# SparkFun_Ambient_Light_Sensor_VEML6030.net
KiCad netlist of a schematic drawn in EAGLE
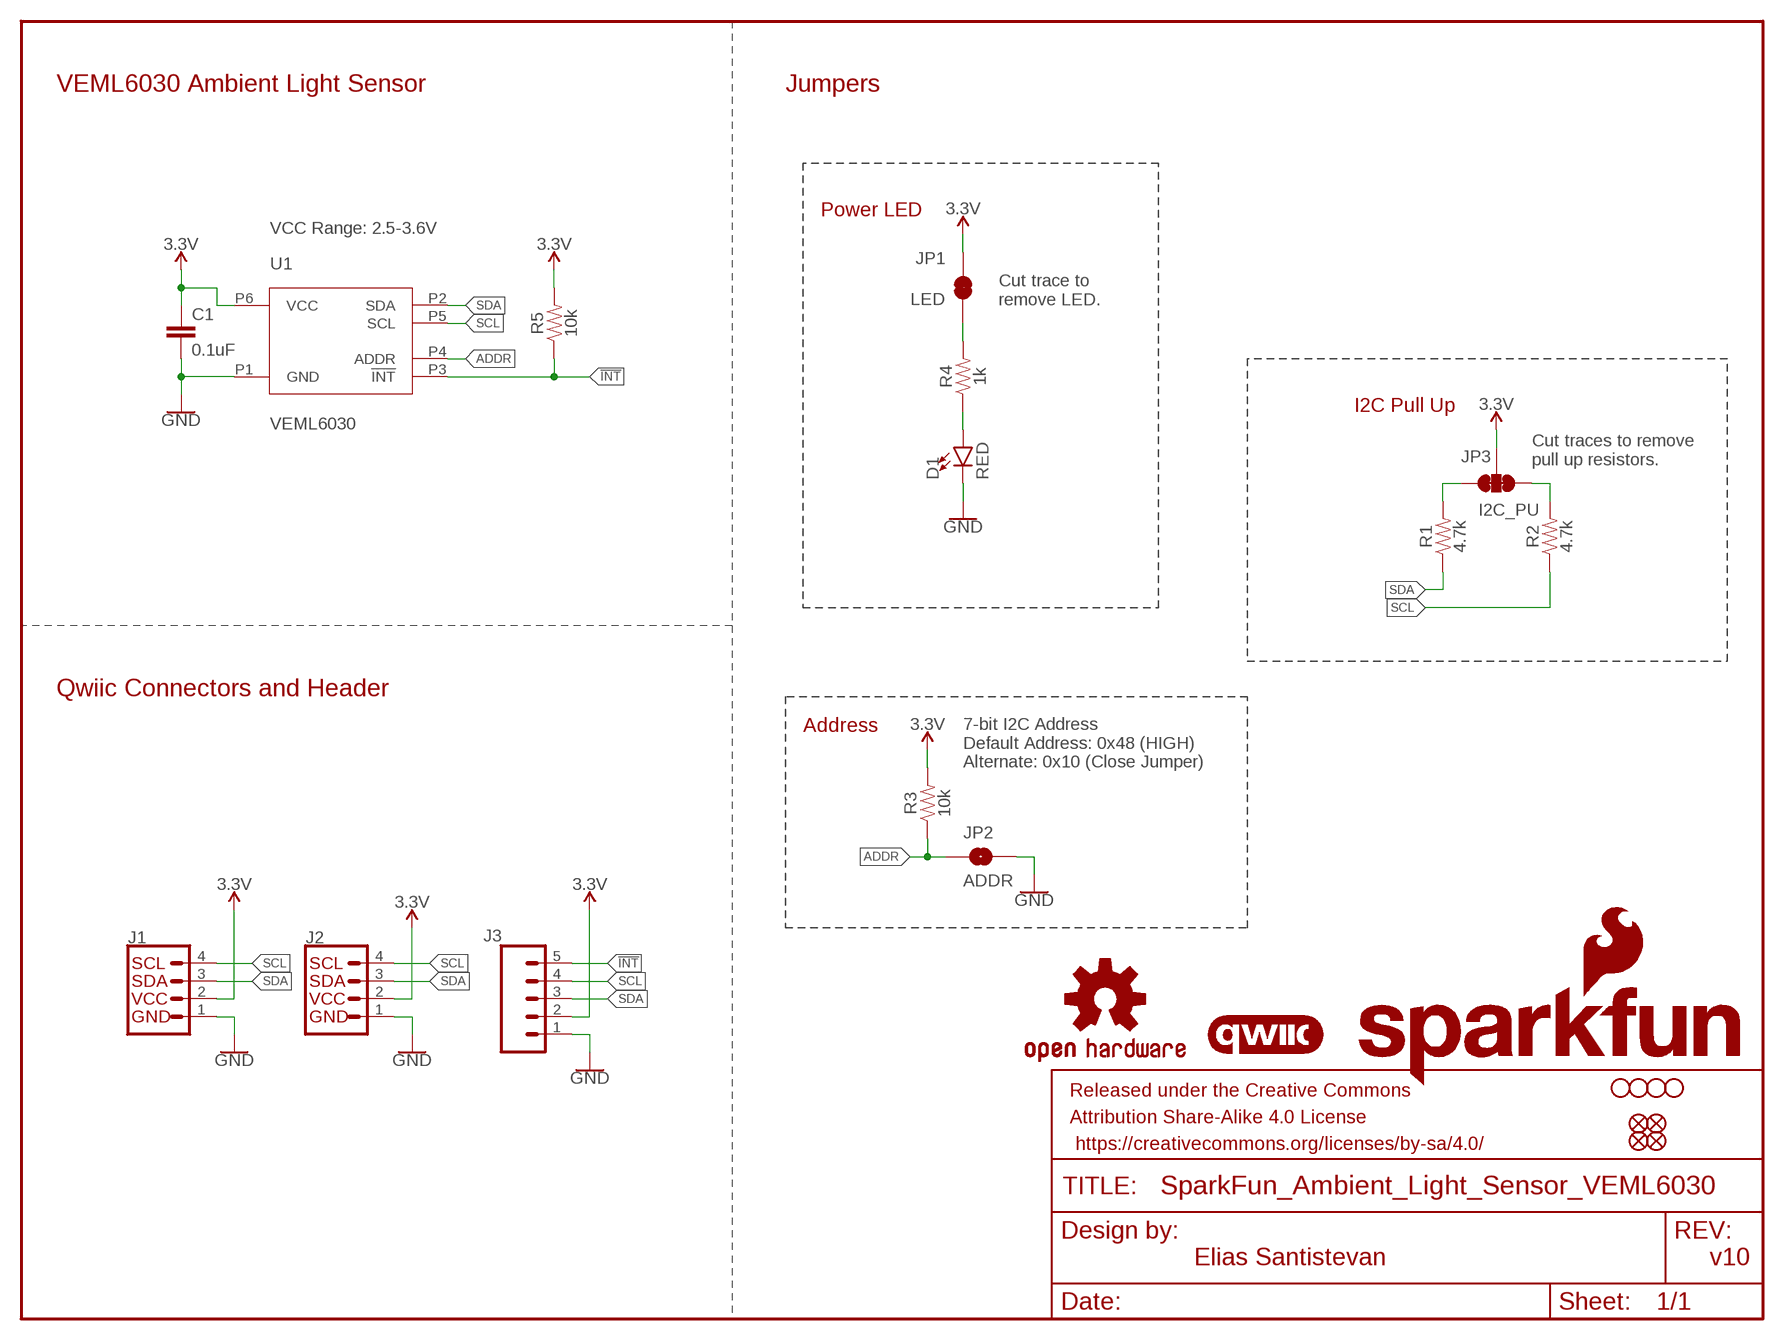
[diagram p0: schematic, sheet 1]

(export (version "E")
  (design (tool "Eeschema 10.0.6"))
  (components
    (comp (ref "C1")
      (value "0.1uF")
      (footprint "eagle-import:0603")
      (libsource (lib "eagle-import") (part "0.1UF-0603-25V-(+80/-20%)"))
    )
    (comp (ref "D1")
      (value "RED")
      (footprint "eagle-import:LED-0603")
      (libsource (lib "eagle-import") (part "LED-RED0603"))
    )
    (comp (ref "FD1")
      (value "FIDUCIAL1X2")
      (footprint "eagle-import:FIDUCIAL-1X2")
      (libsource (lib "eagle-import") (part "FIDUCIAL1X2"))
    )
    (comp (ref "FD2")
      (value "FIDUCIAL1X2")
      (footprint "eagle-import:FIDUCIAL-1X2")
      (libsource (lib "eagle-import") (part "FIDUCIAL1X2"))
    )
    (comp (ref "FD3")
      (value "FIDUCIAL1X2")
      (footprint "eagle-import:FIDUCIAL-1X2")
      (libsource (lib "eagle-import") (part "FIDUCIAL1X2"))
    )
    (comp (ref "FD4")
      (value "FIDUCIAL1X2")
      (footprint "eagle-import:FIDUCIAL-1X2")
      (libsource (lib "eagle-import") (part "FIDUCIAL1X2"))
    )
    (comp (ref "FRAME1")
      (value "FRAME-LETTER")
      (footprint "eagle-import:CREATIVE_COMMONS")
      (libsource (lib "eagle-import") (part "FRAME-LETTER"))
    )
    (comp (ref "H1")
      (value "STAND-OFFTIGHT")
      (footprint "eagle-import:STAND-OFF-TIGHT")
      (libsource (lib "eagle-import") (part "STAND-OFFTIGHT"))
    )
    (comp (ref "H2")
      (value "STAND-OFFTIGHT")
      (footprint "eagle-import:STAND-OFF-TIGHT")
      (libsource (lib "eagle-import") (part "STAND-OFFTIGHT"))
    )
    (comp (ref "H3")
      (value "STAND-OFFTIGHT")
      (footprint "eagle-import:STAND-OFF-TIGHT")
      (libsource (lib "eagle-import") (part "STAND-OFFTIGHT"))
    )
    (comp (ref "H4")
      (value "STAND-OFFTIGHT")
      (footprint "eagle-import:STAND-OFF-TIGHT")
      (libsource (lib "eagle-import") (part "STAND-OFFTIGHT"))
    )
    (comp (ref "J1")
      (value "QWIIC_CONNECTORJS-1MM")
      (footprint "eagle-import:JST04_1MM_RA")
      (libsource (lib "eagle-import") (part "QWIIC_CONNECTORJS-1MM"))
    )
    (comp (ref "J2")
      (value "QWIIC_CONNECTORJS-1MM")
      (footprint "eagle-import:JST04_1MM_RA")
      (libsource (lib "eagle-import") (part "QWIIC_CONNECTORJS-1MM"))
    )
    (comp (ref "J3")
      (value "CONN_05NO_SILK")
      (footprint "eagle-import:1X05_NO_SILK")
      (libsource (lib "eagle-import") (part "CONN_05NO_SILK"))
    )
    (comp (ref "JP1")
      (value "LED")
      (footprint "eagle-import:SMT-JUMPER_2_NC_TRACE_SILK")
      (libsource (lib "eagle-import") (part "JUMPER-SMT_2_NC_TRACE_SILK"))
    )
    (comp (ref "JP2")
      (value "ADDR")
      (footprint "eagle-import:SMT-JUMPER_2_NO_SILK")
      (libsource (lib "eagle-import") (part "JUMPER-SMT_2_NO_SILK"))
    )
    (comp (ref "JP3")
      (value "I2C_PU")
      (footprint "eagle-import:SMT-JUMPER_3_2-NC_TRACE_SILK")
      (libsource (lib "eagle-import") (part "JUMPER-SMT_3_2-NC_TRACE_SILK"))
    )
    (comp (ref "LOGO1")
      (value "SFE_LOGO_NAME_FLAME.1_INCH")
      (footprint "eagle-import:SFE_LOGO_NAME_FLAME_.1")
      (libsource (lib "eagle-import") (part "SFE_LOGO_NAME_FLAME.1_INCH"))
    )
    (comp (ref "LOGO2")
      (value "OSHW-LOGOS")
      (footprint "eagle-import:OSHW-LOGO-S")
      (libsource (lib "eagle-import") (part "OSHW-LOGOS"))
    )
    (comp (ref "R1")
      (value "4.7k")
      (footprint "eagle-import:0603")
      (libsource (lib "eagle-import") (part "4.7KOHM-0603-1/10W-1%"))
    )
    (comp (ref "R2")
      (value "4.7k")
      (footprint "eagle-import:0603")
      (libsource (lib "eagle-import") (part "4.7KOHM-0603-1/10W-1%"))
    )
    (comp (ref "R3")
      (value "10k")
      (footprint "eagle-import:0603")
      (libsource (lib "eagle-import") (part "10KOHM-0603-1/10W-1%"))
    )
    (comp (ref "R4")
      (value "1k")
      (footprint "eagle-import:0603")
      (libsource (lib "eagle-import") (part "1KOHM-0603-1/10W-1%"))
    )
    (comp (ref "R5")
      (value "10k")
      (footprint "eagle-import:0603")
      (libsource (lib "eagle-import") (part "10KOHM-0603-1/10W-1%"))
    )
    (comp (ref "U$1")
      (value "QWIIC_LOGO_5MM")
      (footprint "eagle-import:QWIIC_5MM")
      (libsource (lib "eagle-import") (part "QWIIC_LOGO_5MM"))
    )
    (comp (ref "U1")
      (value "VEML6030")
      (footprint "eagle-import:VEML6030")
      (libsource (lib "eagle-import") (part "VEML6030"))
    )
  )
  (nets
    (net (code "1") (name "/~{INT}") (class "Default")
      (node (ref "J3") (pin "5") (pinfunction "5_5") (pintype "passive"))
      (node (ref "R5") (pin "1") (pinfunction "1_1") (pintype "passive"))
      (node (ref "U1") (pin "P3") (pinfunction "~{INT}_P3") (pintype "output"))
    )
    (net (code "2") (name "3.3V") (class "Default")
      (node (ref "C1") (pin "1") (pinfunction "1_1") (pintype "passive"))
      (node (ref "J1") (pin "2") (pinfunction "2_2") (pintype "power_in"))
      (node (ref "J2") (pin "2") (pinfunction "2_2") (pintype "power_in"))
      (node (ref "J3") (pin "2") (pinfunction "2_2") (pintype "passive"))
      (node (ref "JP1") (pin "2") (pinfunction "2_2") (pintype "passive"))
      (node (ref "JP3") (pin "2") (pinfunction "2_2") (pintype "passive"))
      (node (ref "R3") (pin "2") (pinfunction "2_2") (pintype "passive"))
      (node (ref "R5") (pin "2") (pinfunction "2_2") (pintype "passive"))
      (node (ref "U1") (pin "P6") (pinfunction "VCC_P6") (pintype "power_in"))
    )
    (net (code "3") (name "ADDR") (class "Default")
      (node (ref "JP2") (pin "1") (pinfunction "1_1") (pintype "passive"))
      (node (ref "R3") (pin "1") (pinfunction "1_1") (pintype "passive"))
      (node (ref "U1") (pin "P4") (pinfunction "ADDR_P4") (pintype "bidirectional"))
    )
    (net (code "4") (name "GND") (class "Default")
      (node (ref "C1") (pin "2") (pinfunction "2_2") (pintype "passive"))
      (node (ref "D1") (pin "C") (pinfunction "C_C") (pintype "passive"))
      (node (ref "J1") (pin "1") (pinfunction "1_1") (pintype "power_in"))
      (node (ref "J2") (pin "1") (pinfunction "1_1") (pintype "power_in"))
      (node (ref "J3") (pin "1") (pinfunction "1_1") (pintype "passive"))
      (node (ref "JP2") (pin "2") (pinfunction "2_2") (pintype "passive"))
      (node (ref "U1") (pin "P1") (pinfunction "GND_P1") (pintype "power_in"))
    )
    (net (code "5") (name "Net-(D1-PadA)") (class "Default")
      (node (ref "D1") (pin "A") (pinfunction "A_A") (pintype "passive"))
      (node (ref "R4") (pin "1") (pinfunction "1_1") (pintype "passive"))
    )
    (net (code "6") (name "Net-(JP1-Pad1)") (class "Default")
      (node (ref "JP1") (pin "1") (pinfunction "1_1") (pintype "passive"))
      (node (ref "R4") (pin "2") (pinfunction "2_2") (pintype "passive"))
    )
    (net (code "7") (name "Net-(JP3-Pad1)") (class "Default")
      (node (ref "JP3") (pin "1") (pinfunction "1_1") (pintype "passive"))
      (node (ref "R2") (pin "2") (pinfunction "2_2") (pintype "passive"))
    )
    (net (code "8") (name "Net-(JP3-Pad3)") (class "Default")
      (node (ref "JP3") (pin "3") (pinfunction "3_3") (pintype "passive"))
      (node (ref "R1") (pin "2") (pinfunction "2_2") (pintype "passive"))
    )
    (net (code "9") (name "SCL") (class "Default")
      (node (ref "J1") (pin "4") (pinfunction "4_4") (pintype "passive"))
      (node (ref "J2") (pin "4") (pinfunction "4_4") (pintype "passive"))
      (node (ref "J3") (pin "4") (pinfunction "4_4") (pintype "passive"))
      (node (ref "R2") (pin "1") (pinfunction "1_1") (pintype "passive"))
      (node (ref "U1") (pin "P5") (pinfunction "SCL_P5") (pintype "bidirectional"))
    )
    (net (code "10") (name "SDA") (class "Default")
      (node (ref "J1") (pin "3") (pinfunction "3_3") (pintype "passive"))
      (node (ref "J2") (pin "3") (pinfunction "3_3") (pintype "passive"))
      (node (ref "J3") (pin "3") (pinfunction "3_3") (pintype "passive"))
      (node (ref "R1") (pin "1") (pinfunction "1_1") (pintype "passive"))
      (node (ref "U1") (pin "P2") (pinfunction "SDA_P2") (pintype "bidirectional"))
    )
  )
)
